# RF.net
KiCad netlist of a schematic drawn in Altium Designer
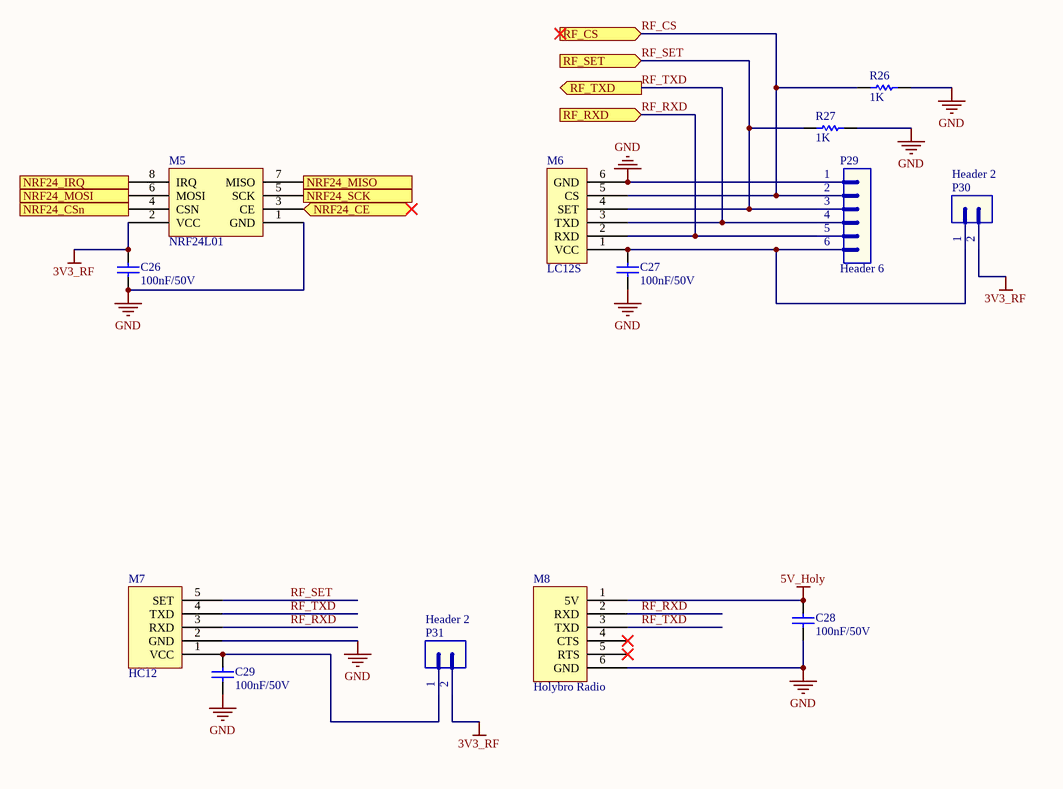
[diagram p0: RF.SchDoc]

(export (version "E")
  (design (tool "Eeschema 10.0.6"))
  (components
    (comp (ref "C26")
      (value "100nF/50V")
      (footprint "CAP-SM-0805")
      (description "CAP CER 0.1UF 50V Y5V 0805")
      (fields
        (field (name "MANUFACTURER") "Samsung Electro-Mechanics")
        (field (name "MANUFACTURER PART NUMBER") "CL21F104ZBCNNNC")
      )
      (libsource (lib "Capacitor") (part "Cap-100nF-50V-0805"))
    )
    (comp (ref "C27")
      (value "100nF/50V")
      (footprint "CAP-SM-0805")
      (description "CAP CER 0.1UF 50V Y5V 0805")
      (fields
        (field (name "MANUFACTURER") "Samsung Electro-Mechanics")
        (field (name "MANUFACTURER PART NUMBER") "CL21F104ZBCNNNC")
      )
      (libsource (lib "Capacitor") (part "Cap-100nF-50V-0805"))
    )
    (comp (ref "C28")
      (value "100nF/50V")
      (footprint "CAP-SM-0805")
      (description "CAP CER 0.1UF 50V Y5V 0805")
      (fields
        (field (name "MANUFACTURER") "Samsung Electro-Mechanics")
        (field (name "MANUFACTURER PART NUMBER") "CL21F104ZBCNNNC")
      )
      (libsource (lib "Capacitor") (part "Cap-100nF-50V-0805"))
    )
    (comp (ref "C29")
      (value "100nF/50V")
      (footprint "CAP-SM-0805")
      (description "CAP CER 0.1UF 50V Y5V 0805")
      (fields
        (field (name "MANUFACTURER") "Samsung Electro-Mechanics")
        (field (name "MANUFACTURER PART NUMBER") "CL21F104ZBCNNNC")
      )
      (libsource (lib "Capacitor") (part "Cap-100nF-50V-0805"))
    )
    (comp (ref "M5")
      (value "NRF24L01")
      (footprint "NRF24L01")
      (fields (field (name "LOCAL SUPPLIER PART NUMBER") "HS000888"))
      (libsource (lib "PIFWRoBot") (part "NRF24L01"))
    )
    (comp (ref "M6")
      (value "LC12S")
      (footprint "LC12S")
      (fields (field (name "LOCAL SUPPLIER PART NUMBER") "HS000895"))
      (libsource (lib "PIFWRoBot") (part "LC12S"))
    )
    (comp (ref "M7")
      (value "HC12")
      (footprint "HC12")
      (fields (field (name "LOCAL SUPPLIER PART NUMBER") "HS000897"))
      (libsource (lib "PIFWRoBot") (part "HC12"))
    )
    (comp (ref "M8")
      (value "Holybro Radio")
      (footprint "HOLYBRO RADIO")
      (libsource (lib "PIFWRoBot") (part "HOLYBRO RADIO"))
    )
    (comp (ref "P29")
      (value "Header 6")
      (footprint "JP6")
      (description "Header, 6-Pin")
      (fields (field (name "PUBLISHER") "Altium Limited"))
      (libsource (lib "Header-connector") (part "Header 6"))
    )
    (comp (ref "P30")
      (value "Header 2")
      (footprint "JP2")
      (description "Header, 2-Pin")
      (fields (field (name "PUBLISHER") "Altium Limited"))
      (libsource (lib "Header-connector") (part "Header 2"))
    )
    (comp (ref "P31")
      (value "Header 2")
      (footprint "JP2")
      (description "Header, 2-Pin")
      (fields (field (name "PUBLISHER") "Altium Limited"))
      (libsource (lib "Header-connector") (part "Header 2"))
    )
    (comp (ref "R26")
      (value "1K")
      (footprint "Resistor:RES-SM-0805")
      (description "RES 1K OHM 1% 1/4W 0805")
      (fields
        (field (name "MANUFACTURER") "Stackpole Electronics Inc")
        (field (name "MANUFACTURER PART NUMBER") "RNCP0805FTD1K00")
      )
      (libsource (lib "Resistor") (part "Res-1K-0805"))
    )
    (comp (ref "R27")
      (value "1K")
      (footprint "Resistor:RES-SM-0805")
      (description "RES 1K OHM 1% 1/4W 0805")
      (fields
        (field (name "MANUFACTURER") "Stackpole Electronics Inc")
        (field (name "MANUFACTURER PART NUMBER") "RNCP0805FTD1K00")
      )
      (libsource (lib "Resistor") (part "Res-1K-0805"))
    )
  )
  (nets
    (net (code "1") (name "/NRF24_CE") (class "Default")
      (node (ref "M5") (pin "3") (pinfunction "CE_3") (pintype "passive"))
    )
    (net (code "2") (name "/NRF24_CSn") (class "Default")
      (node (ref "M5") (pin "4") (pinfunction "CSN_4") (pintype "passive"))
    )
    (net (code "3") (name "/NRF24_IRQ") (class "Default")
      (node (ref "M5") (pin "8") (pinfunction "IRQ_8") (pintype "passive"))
    )
    (net (code "4") (name "/NRF24_MISO") (class "Default")
      (node (ref "M5") (pin "7") (pinfunction "MISO_7") (pintype "passive"))
    )
    (net (code "5") (name "/NRF24_MOSI") (class "Default")
      (node (ref "M5") (pin "6") (pinfunction "MOSI_6") (pintype "passive"))
    )
    (net (code "6") (name "/NRF24_SCK") (class "Default")
      (node (ref "M5") (pin "5") (pinfunction "SCK_5") (pintype "passive"))
    )
    (net (code "7") (name "/RF_CS") (class "Default")
      (node (ref "M6") (pin "5") (pinfunction "CS_5") (pintype "passive"))
      (node (ref "P29") (pin "2") (pinfunction "2_2") (pintype "passive"))
      (node (ref "R26") (pin "1") (pinfunction "1_1") (pintype "passive"))
    )
    (net (code "8") (name "/RF_RXD") (class "Default")
      (node (ref "M6") (pin "2") (pinfunction "RXD_2") (pintype "passive"))
      (node (ref "M7") (pin "3") (pinfunction "RXD_3") (pintype "passive"))
      (node (ref "M8") (pin "2") (pinfunction "RXD_2") (pintype "passive"))
      (node (ref "P29") (pin "5") (pinfunction "5_5") (pintype "passive"))
    )
    (net (code "9") (name "/RF_SET") (class "Default")
      (node (ref "M6") (pin "4") (pinfunction "SET_4") (pintype "passive"))
      (node (ref "M7") (pin "5") (pinfunction "SET_5") (pintype "passive"))
      (node (ref "P29") (pin "3") (pinfunction "3_3") (pintype "passive"))
      (node (ref "R27") (pin "1") (pinfunction "1_1") (pintype "passive"))
    )
    (net (code "10") (name "/RF_TXD") (class "Default")
      (node (ref "M6") (pin "3") (pinfunction "TXD_3") (pintype "passive"))
      (node (ref "M7") (pin "4") (pinfunction "TXD_4") (pintype "passive"))
      (node (ref "M8") (pin "3") (pinfunction "TXD_3") (pintype "passive"))
      (node (ref "P29") (pin "4") (pinfunction "4_4") (pintype "passive"))
    )
    (net (code "11") (name "3V3_RF") (class "Default")
      (node (ref "C26") (pin "2") (pinfunction "2_2") (pintype "passive"))
      (node (ref "M5") (pin "2") (pinfunction "VCC_2") (pintype "passive"))
      (node (ref "P30") (pin "2") (pinfunction "2_2") (pintype "passive"))
      (node (ref "P31") (pin "2") (pinfunction "2_2") (pintype "passive"))
    )
    (net (code "12") (name "5V_Holy") (class "Default")
      (node (ref "C28") (pin "2") (pinfunction "2_2") (pintype "passive"))
      (node (ref "M8") (pin "1") (pinfunction "5V_1") (pintype "passive"))
    )
    (net (code "13") (name "GND") (class "Default")
      (node (ref "C26") (pin "1") (pinfunction "1_1") (pintype "passive"))
      (node (ref "C27") (pin "1") (pinfunction "1_1") (pintype "passive"))
      (node (ref "C28") (pin "1") (pinfunction "1_1") (pintype "passive"))
      (node (ref "C29") (pin "1") (pinfunction "1_1") (pintype "passive"))
      (node (ref "M5") (pin "1") (pinfunction "GND_1") (pintype "passive"))
      (node (ref "M6") (pin "6") (pinfunction "GND_6") (pintype "passive"))
      (node (ref "M7") (pin "2") (pinfunction "GND_2") (pintype "passive"))
      (node (ref "M8") (pin "6") (pinfunction "GND_6") (pintype "passive"))
      (node (ref "P29") (pin "1") (pinfunction "1_1") (pintype "passive"))
      (node (ref "R26") (pin "2") (pinfunction "2_2") (pintype "passive"))
      (node (ref "R27") (pin "2") (pinfunction "2_2") (pintype "passive"))
    )
    (net (code "14") (name "Net-(M6-VCC)") (class "Default")
      (node (ref "C27") (pin "2") (pinfunction "2_2") (pintype "passive"))
      (node (ref "M6") (pin "1") (pinfunction "VCC_1") (pintype "passive"))
      (node (ref "P29") (pin "6") (pinfunction "6_6") (pintype "passive"))
      (node (ref "P30") (pin "1") (pinfunction "1_1") (pintype "passive"))
    )
    (net (code "15") (name "Net-(M7-VCC)") (class "Default")
      (node (ref "C29") (pin "2") (pinfunction "2_2") (pintype "passive"))
      (node (ref "M7") (pin "1") (pinfunction "VCC_1") (pintype "passive"))
      (node (ref "P31") (pin "1") (pinfunction "1_1") (pintype "passive"))
    )
    (net (code "16") (name "unconnected-(M8-CTS-Pad4)") (class "Default")
      (node (ref "M8") (pin "4") (pinfunction "CTS_4") (pintype "passive+no_connect"))
    )
    (net (code "17") (name "unconnected-(M8-RTS-Pad5)") (class "Default")
      (node (ref "M8") (pin "5") (pinfunction "RTS_5") (pintype "passive+no_connect"))
    )
  )
)
